# driver-board.net
KiCad netlist of a schematic drawn in EAGLE
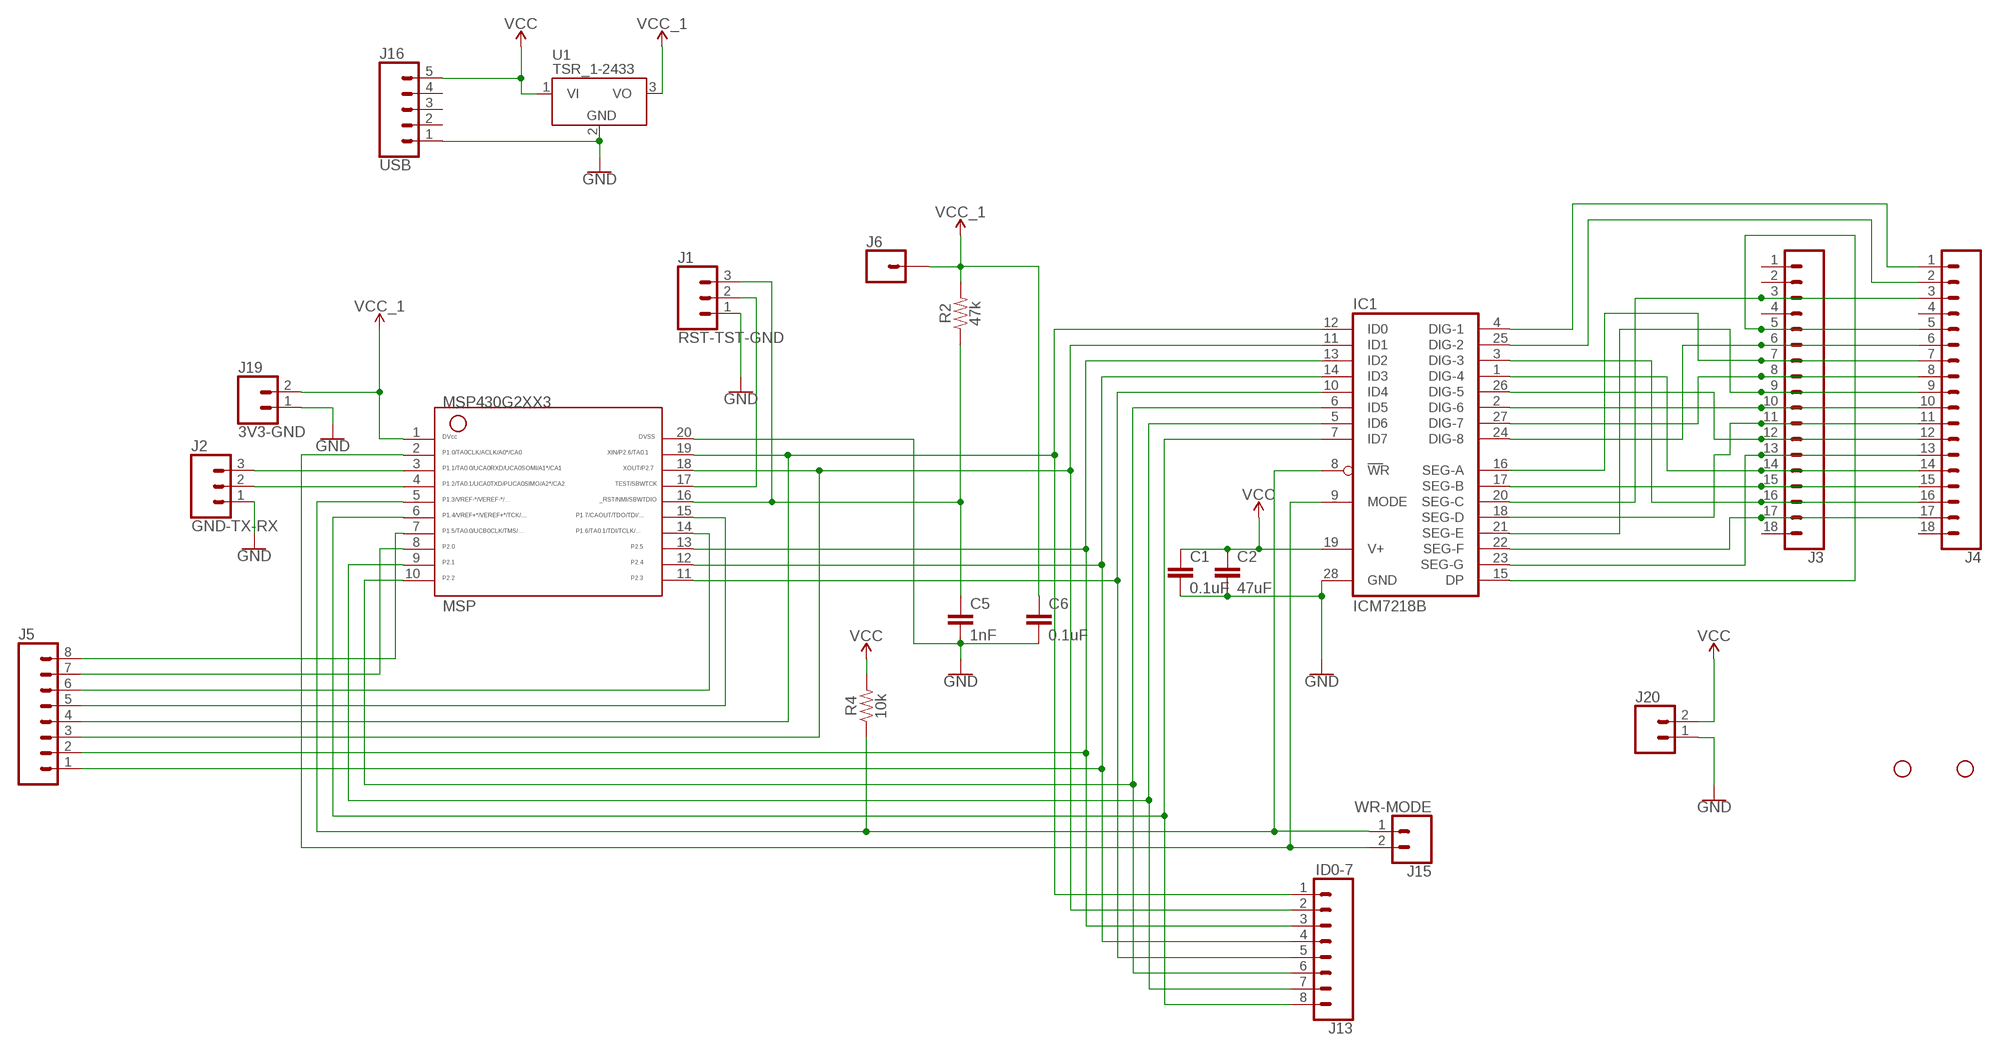
[diagram p0: schematic, sheet 1]

(export (version "E")
  (design (tool "Eeschema 10.0.6"))
  (components
    (comp (ref "C1")
      (value "0.1uF")
      (footprint "eagle-import:C2.5-2")
      (libsource (lib "eagle-import") (part "C2.5/2"))
    )
    (comp (ref "C2")
      (value "47uF")
      (footprint "eagle-import:C2.5-5")
      (libsource (lib "eagle-import") (part "C2.5/5"))
    )
    (comp (ref "C5")
      (value "1nF")
      (footprint "eagle-import:C5B2.5")
      (libsource (lib "eagle-import") (part "C5/2.5"))
    )
    (comp (ref "C6")
      (value "0.1uF")
      (footprint "eagle-import:C5B2.5")
      (libsource (lib "eagle-import") (part "C5/2.5"))
    )
    (comp (ref "H1")
      (value "STAND-OFF")
      (footprint "eagle-import:STAND-OFF")
      (libsource (lib "eagle-import") (part "STAND-OFF"))
    )
    (comp (ref "H2")
      (value "STAND-OFF")
      (footprint "eagle-import:STAND-OFF")
      (libsource (lib "eagle-import") (part "STAND-OFF"))
    )
    (comp (ref "IC1")
      (value "ICM7218B")
      (footprint "eagle-import:DIL28-6")
      (fields (field (name "MF") "INTERSIL") (field (name "MPN") "ICM7218BIJI"))
      (libsource (lib "eagle-import") (part "ICM7218B"))
    )
    (comp (ref "J1")
      (value "RST-TST-GND")
      (footprint "eagle-import:1X03_LOCK")
      (libsource (lib "eagle-import") (part "CONN_03LOCK"))
    )
    (comp (ref "J2")
      (value "GND-TX-RX")
      (footprint "eagle-import:1X03_LOCK")
      (libsource (lib "eagle-import") (part "CONN_03LOCK"))
    )
    (comp (ref "J3")
      (value "CONN_18")
      (footprint "eagle-import:1X18")
      (libsource (lib "eagle-import") (part "CONN_18"))
    )
    (comp (ref "J4")
      (value "CONN_18")
      (footprint "eagle-import:1X18")
      (libsource (lib "eagle-import") (part "CONN_18"))
    )
    (comp (ref "J5")
      (value "CONN_08\"")
      (footprint "eagle-import:1X08")
      (libsource (lib "eagle-import") (part "CONN_08{dblquote}"))
    )
    (comp (ref "J6")
      (value "CONN_01")
      (footprint "eagle-import:1X01")
      (libsource (lib "eagle-import") (part "CONN_01"))
    )
    (comp (ref "J13")
      (value "ID0-7")
      (footprint "eagle-import:1X08_LOCK")
      (libsource (lib "eagle-import") (part "CONN_08LOCK"))
    )
    (comp (ref "J15")
      (value "WR-MODE")
      (footprint "eagle-import:1X02")
      (libsource (lib "eagle-import") (part "CONN_02"))
    )
    (comp (ref "J16")
      (value "USB")
      (footprint "eagle-import:1X05_LOCK")
      (libsource (lib "eagle-import") (part "CONN_05LOCK"))
    )
    (comp (ref "J19")
      (value "3V3-GND")
      (footprint "eagle-import:1X02")
      (libsource (lib "eagle-import") (part "CONN_02"))
    )
    (comp (ref "J20")
      (value "CONN_02")
      (footprint "eagle-import:1X02")
      (libsource (lib "eagle-import") (part "CONN_02"))
    )
    (comp (ref "MSP")
      (value "G2XX3---N20")
      (footprint "eagle-import:N20")
      (libsource (lib "eagle-import") (part "G2XX3---N20"))
    )
    (comp (ref "R2")
      (value "47k")
      (footprint "eagle-import:AXIAL-0.3")
      (libsource (lib "eagle-import") (part "1KOHM-HORIZ-1/4W-1%"))
    )
    (comp (ref "R4")
      (value "10k")
      (footprint "eagle-import:AXIAL-0.3")
      (libsource (lib "eagle-import") (part "10KOHM-HORIZ-1/4W-1%"))
    )
    (comp (ref "U1")
      (value "TSR_1-2433")
      (footprint "eagle-import:TSR-1")
      (libsource (lib "eagle-import") (part "TSR_1-2433"))
    )
  )
  (nets
    (net (code "1") (name "GND") (class "Default")
      (node (ref "C1") (pin "2") (pinfunction "2_2") (pintype "passive"))
      (node (ref "C2") (pin "2") (pinfunction "2_2") (pintype "passive"))
      (node (ref "C5") (pin "2") (pinfunction "2_2") (pintype "passive"))
      (node (ref "C6") (pin "2") (pinfunction "2_2") (pintype "passive"))
      (node (ref "IC1") (pin "28") (pinfunction "GND_28") (pintype "power_in"))
      (node (ref "J1") (pin "1") (pinfunction "1_1") (pintype "passive"))
      (node (ref "J16") (pin "1") (pinfunction "1_1") (pintype "passive"))
      (node (ref "J19") (pin "1") (pinfunction "1_1") (pintype "passive"))
      (node (ref "J2") (pin "1") (pinfunction "1_1") (pintype "passive"))
      (node (ref "J20") (pin "1") (pinfunction "1_1") (pintype "passive"))
      (node (ref "MSP") (pin "20") (pinfunction "20_20") (pintype "bidirectional"))
      (node (ref "U1") (pin "2") (pinfunction "GND_2") (pintype "power_in"))
    )
    (net (code "2") (name "Net-(IC1-DIG-1)") (class "Default")
      (node (ref "IC1") (pin "4") (pinfunction "DIG-1_4") (pintype "output"))
      (node (ref "J4") (pin "1") (pinfunction "1_1") (pintype "passive"))
    )
    (net (code "3") (name "Net-(IC1-DIG-2)") (class "Default")
      (node (ref "IC1") (pin "25") (pinfunction "DIG-2_25") (pintype "output"))
      (node (ref "J4") (pin "2") (pinfunction "2_2") (pintype "passive"))
    )
    (net (code "4") (name "Net-(IC1-DIG-3)") (class "Default")
      (node (ref "IC1") (pin "3") (pinfunction "DIG-3_3") (pintype "output"))
      (node (ref "J3") (pin "16") (pinfunction "16_16") (pintype "passive"))
      (node (ref "J4") (pin "16") (pinfunction "16_16") (pintype "passive"))
    )
    (net (code "5") (name "Net-(IC1-DIG-4)") (class "Default")
      (node (ref "IC1") (pin "1") (pinfunction "DIG-4_1") (pintype "output"))
      (node (ref "J3") (pin "14") (pinfunction "14_14") (pintype "passive"))
      (node (ref "J4") (pin "14") (pinfunction "14_14") (pintype "passive"))
    )
    (net (code "6") (name "Net-(IC1-DIG-5)") (class "Default")
      (node (ref "IC1") (pin "26") (pinfunction "DIG-5_26") (pintype "output"))
      (node (ref "J3") (pin "12") (pinfunction "12_12") (pintype "passive"))
      (node (ref "J4") (pin "12") (pinfunction "12_12") (pintype "passive"))
    )
    (net (code "7") (name "Net-(IC1-DIG-6)") (class "Default")
      (node (ref "IC1") (pin "2") (pinfunction "DIG-6_2") (pintype "output"))
      (node (ref "J3") (pin "10") (pinfunction "10_10") (pintype "passive"))
      (node (ref "J4") (pin "10") (pinfunction "10_10") (pintype "passive"))
    )
    (net (code "8") (name "Net-(IC1-DIG-7)") (class "Default")
      (node (ref "IC1") (pin "27") (pinfunction "DIG-7_27") (pintype "output"))
      (node (ref "J3") (pin "8") (pinfunction "8_8") (pintype "passive"))
      (node (ref "J4") (pin "8") (pinfunction "8_8") (pintype "passive"))
    )
    (net (code "9") (name "Net-(IC1-DIG-8)") (class "Default")
      (node (ref "IC1") (pin "24") (pinfunction "DIG-8_24") (pintype "output"))
      (node (ref "J3") (pin "6") (pinfunction "6_6") (pintype "passive"))
      (node (ref "J4") (pin "6") (pinfunction "6_6") (pintype "passive"))
    )
    (net (code "10") (name "Net-(IC1-DP)") (class "Default")
      (node (ref "IC1") (pin "15") (pinfunction "DP_15") (pintype "output"))
      (node (ref "J3") (pin "5") (pinfunction "5_5") (pintype "passive"))
      (node (ref "J4") (pin "5") (pinfunction "5_5") (pintype "passive"))
    )
    (net (code "11") (name "Net-(IC1-ID0)") (class "Default")
      (node (ref "IC1") (pin "12") (pinfunction "ID0_12") (pintype "input"))
      (node (ref "J13") (pin "1") (pinfunction "1_1") (pintype "passive"))
      (node (ref "J5") (pin "4") (pinfunction "4_4") (pintype "passive"))
      (node (ref "MSP") (pin "19") (pinfunction "19_19") (pintype "bidirectional"))
    )
    (net (code "12") (name "Net-(IC1-ID1)") (class "Default")
      (node (ref "IC1") (pin "11") (pinfunction "ID1_11") (pintype "input"))
      (node (ref "J13") (pin "2") (pinfunction "2_2") (pintype "passive"))
      (node (ref "J5") (pin "3") (pinfunction "3_3") (pintype "passive"))
      (node (ref "MSP") (pin "18") (pinfunction "18_18") (pintype "bidirectional"))
    )
    (net (code "13") (name "Net-(IC1-ID2)") (class "Default")
      (node (ref "IC1") (pin "13") (pinfunction "ID2_13") (pintype "input"))
      (node (ref "J13") (pin "3") (pinfunction "3_3") (pintype "passive"))
      (node (ref "J5") (pin "2") (pinfunction "2_2") (pintype "passive"))
      (node (ref "MSP") (pin "13") (pinfunction "13_13") (pintype "bidirectional"))
    )
    (net (code "14") (name "Net-(IC1-ID3)") (class "Default")
      (node (ref "IC1") (pin "14") (pinfunction "ID3_14") (pintype "input"))
      (node (ref "J13") (pin "4") (pinfunction "4_4") (pintype "passive"))
      (node (ref "J5") (pin "1") (pinfunction "1_1") (pintype "passive"))
      (node (ref "MSP") (pin "12") (pinfunction "12_12") (pintype "bidirectional"))
    )
    (net (code "15") (name "Net-(IC1-ID4)") (class "Default")
      (node (ref "IC1") (pin "10") (pinfunction "ID4_10") (pintype "input"))
      (node (ref "J13") (pin "5") (pinfunction "5_5") (pintype "passive"))
      (node (ref "MSP") (pin "11") (pinfunction "11_11") (pintype "bidirectional"))
    )
    (net (code "16") (name "Net-(IC1-ID5)") (class "Default")
      (node (ref "IC1") (pin "6") (pinfunction "ID5_6") (pintype "input"))
      (node (ref "J13") (pin "6") (pinfunction "6_6") (pintype "passive"))
      (node (ref "MSP") (pin "10") (pinfunction "10_10") (pintype "bidirectional"))
    )
    (net (code "17") (name "Net-(IC1-ID6)") (class "Default")
      (node (ref "IC1") (pin "5") (pinfunction "ID6_5") (pintype "input"))
      (node (ref "J13") (pin "7") (pinfunction "7_7") (pintype "passive"))
      (node (ref "MSP") (pin "9") (pinfunction "9_9") (pintype "bidirectional"))
    )
    (net (code "18") (name "Net-(IC1-ID7)") (class "Default")
      (node (ref "IC1") (pin "7") (pinfunction "ID7_7") (pintype "input"))
      (node (ref "J13") (pin "8") (pinfunction "8_8") (pintype "passive"))
      (node (ref "MSP") (pin "6") (pinfunction "6_6") (pintype "bidirectional"))
    )
    (net (code "19") (name "Net-(IC1-MODE)") (class "Default")
      (node (ref "IC1") (pin "9") (pinfunction "MODE_9") (pintype "input"))
      (node (ref "J15") (pin "2") (pinfunction "2_2") (pintype "passive"))
      (node (ref "MSP") (pin "2") (pinfunction "2_2") (pintype "bidirectional"))
    )
    (net (code "20") (name "Net-(IC1-SEG-A)") (class "Default")
      (node (ref "IC1") (pin "16") (pinfunction "SEG-A_16") (pintype "output"))
      (node (ref "J3") (pin "7") (pinfunction "7_7") (pintype "passive"))
      (node (ref "J4") (pin "7") (pinfunction "7_7") (pintype "passive"))
    )
    (net (code "21") (name "Net-(IC1-SEG-B)") (class "Default")
      (node (ref "IC1") (pin "17") (pinfunction "SEG-B_17") (pintype "output"))
      (node (ref "J3") (pin "15") (pinfunction "15_15") (pintype "passive"))
      (node (ref "J4") (pin "15") (pinfunction "15_15") (pintype "passive"))
    )
    (net (code "22") (name "Net-(IC1-SEG-C)") (class "Default")
      (node (ref "IC1") (pin "20") (pinfunction "SEG-C_20") (pintype "output"))
      (node (ref "J3") (pin "3") (pinfunction "3_3") (pintype "passive"))
      (node (ref "J4") (pin "3") (pinfunction "3_3") (pintype "passive"))
    )
    (net (code "23") (name "Net-(IC1-SEG-D)") (class "Default")
      (node (ref "IC1") (pin "18") (pinfunction "SEG-D_18") (pintype "output"))
      (node (ref "J3") (pin "11") (pinfunction "11_11") (pintype "passive"))
      (node (ref "J4") (pin "11") (pinfunction "11_11") (pintype "passive"))
    )
    (net (code "24") (name "Net-(IC1-SEG-E)") (class "Default")
      (node (ref "IC1") (pin "21") (pinfunction "SEG-E_21") (pintype "output"))
      (node (ref "J3") (pin "9") (pinfunction "9_9") (pintype "passive"))
      (node (ref "J4") (pin "9") (pinfunction "9_9") (pintype "passive"))
    )
    (net (code "25") (name "Net-(IC1-SEG-F)") (class "Default")
      (node (ref "IC1") (pin "22") (pinfunction "SEG-F_22") (pintype "output"))
      (node (ref "J3") (pin "17") (pinfunction "17_17") (pintype "passive"))
      (node (ref "J4") (pin "17") (pinfunction "17_17") (pintype "passive"))
    )
    (net (code "26") (name "Net-(IC1-SEG-G)") (class "Default")
      (node (ref "IC1") (pin "23") (pinfunction "SEG-G_23") (pintype "output"))
      (node (ref "J3") (pin "13") (pinfunction "13_13") (pintype "passive"))
      (node (ref "J4") (pin "13") (pinfunction "13_13") (pintype "passive"))
    )
    (net (code "27") (name "Net-(IC1-WR)") (class "Default")
      (node (ref "IC1") (pin "8") (pinfunction "WR_8") (pintype "input"))
      (node (ref "J15") (pin "1") (pinfunction "1_1") (pintype "passive"))
      (node (ref "MSP") (pin "5") (pinfunction "5_5") (pintype "bidirectional"))
      (node (ref "R4") (pin "P$1") (pinfunction "1_P$1") (pintype "passive"))
    )
    (net (code "28") (name "Net-(J1-Pad2)") (class "Default")
      (node (ref "J1") (pin "2") (pinfunction "2_2") (pintype "passive"))
      (node (ref "MSP") (pin "17") (pinfunction "17_17") (pintype "bidirectional"))
    )
    (net (code "29") (name "Net-(J2-Pad2)") (class "Default")
      (node (ref "J2") (pin "2") (pinfunction "2_2") (pintype "passive"))
      (node (ref "MSP") (pin "4") (pinfunction "4_4") (pintype "bidirectional"))
    )
    (net (code "30") (name "Net-(J2-Pad3)") (class "Default")
      (node (ref "J2") (pin "3") (pinfunction "3_3") (pintype "passive"))
      (node (ref "MSP") (pin "3") (pinfunction "3_3") (pintype "bidirectional"))
    )
    (net (code "31") (name "Net-(J5-Pad5)") (class "Default")
      (node (ref "J5") (pin "5") (pinfunction "5_5") (pintype "passive"))
      (node (ref "MSP") (pin "15") (pinfunction "15_15") (pintype "bidirectional"))
    )
    (net (code "32") (name "Net-(J5-Pad6)") (class "Default")
      (node (ref "J5") (pin "6") (pinfunction "6_6") (pintype "passive"))
      (node (ref "MSP") (pin "14") (pinfunction "14_14") (pintype "bidirectional"))
    )
    (net (code "33") (name "Net-(J5-Pad7)") (class "Default")
      (node (ref "J5") (pin "7") (pinfunction "7_7") (pintype "passive"))
      (node (ref "MSP") (pin "8") (pinfunction "8_8") (pintype "bidirectional"))
    )
    (net (code "34") (name "Net-(J5-Pad8)") (class "Default")
      (node (ref "J5") (pin "8") (pinfunction "8_8") (pintype "passive"))
      (node (ref "MSP") (pin "7") (pinfunction "7_7") (pintype "bidirectional"))
    )
    (net (code "35") (name "Net-(R2-1)") (class "Default")
      (node (ref "C5") (pin "1") (pinfunction "1_1") (pintype "passive"))
      (node (ref "J1") (pin "3") (pinfunction "3_3") (pintype "passive"))
      (node (ref "MSP") (pin "16") (pinfunction "16_16") (pintype "bidirectional"))
      (node (ref "R2") (pin "P$1") (pinfunction "1_P$1") (pintype "passive"))
    )
    (net (code "36") (name "VCC") (class "Default")
      (node (ref "C1") (pin "1") (pinfunction "1_1") (pintype "passive"))
      (node (ref "C2") (pin "1") (pinfunction "1_1") (pintype "passive"))
      (node (ref "IC1") (pin "19") (pinfunction "V+_19") (pintype "power_in"))
      (node (ref "J16") (pin "5") (pinfunction "5_5") (pintype "passive"))
      (node (ref "J20") (pin "2") (pinfunction "2_2") (pintype "passive"))
      (node (ref "R4") (pin "P$2") (pinfunction "2_P$2") (pintype "passive"))
      (node (ref "U1") (pin "1") (pinfunction "VI_1") (pintype "power_in"))
    )
    (net (code "37") (name "VCC_1") (class "Default")
      (node (ref "C6") (pin "1") (pinfunction "1_1") (pintype "passive"))
      (node (ref "J19") (pin "2") (pinfunction "2_2") (pintype "passive"))
      (node (ref "J6") (pin "1") (pinfunction "1_1") (pintype "passive"))
      (node (ref "MSP") (pin "1") (pinfunction "1_1") (pintype "bidirectional"))
      (node (ref "R2") (pin "P$2") (pinfunction "2_P$2") (pintype "passive"))
      (node (ref "U1") (pin "3") (pinfunction "VO_3") (pintype "power_in"))
    )
    (net (code "38") (name "unconnected-(J3-Pad1)") (class "Default")
      (node (ref "J3") (pin "1") (pinfunction "1_1") (pintype "passive"))
    )
    (net (code "39") (name "unconnected-(J3-Pad2)") (class "Default")
      (node (ref "J3") (pin "2") (pinfunction "2_2") (pintype "passive"))
    )
    (net (code "40") (name "unconnected-(J3-Pad4)") (class "Default")
      (node (ref "J3") (pin "4") (pinfunction "4_4") (pintype "passive"))
    )
    (net (code "41") (name "unconnected-(J3-Pad18)") (class "Default")
      (node (ref "J3") (pin "18") (pinfunction "18_18") (pintype "passive"))
    )
    (net (code "42") (name "unconnected-(J4-Pad4)") (class "Default")
      (node (ref "J4") (pin "4") (pinfunction "4_4") (pintype "passive"))
    )
    (net (code "43") (name "unconnected-(J4-Pad18)") (class "Default")
      (node (ref "J4") (pin "18") (pinfunction "18_18") (pintype "passive"))
    )
    (net (code "44") (name "unconnected-(J16-Pad2)") (class "Default")
      (node (ref "J16") (pin "2") (pinfunction "2_2") (pintype "passive"))
    )
    (net (code "45") (name "unconnected-(J16-Pad3)") (class "Default")
      (node (ref "J16") (pin "3") (pinfunction "3_3") (pintype "passive"))
    )
    (net (code "46") (name "unconnected-(J16-Pad4)") (class "Default")
      (node (ref "J16") (pin "4") (pinfunction "4_4") (pintype "passive"))
    )
  )
)
